# 01_MAIN.net
KiCad netlist of a schematic drawn in Altium Designer
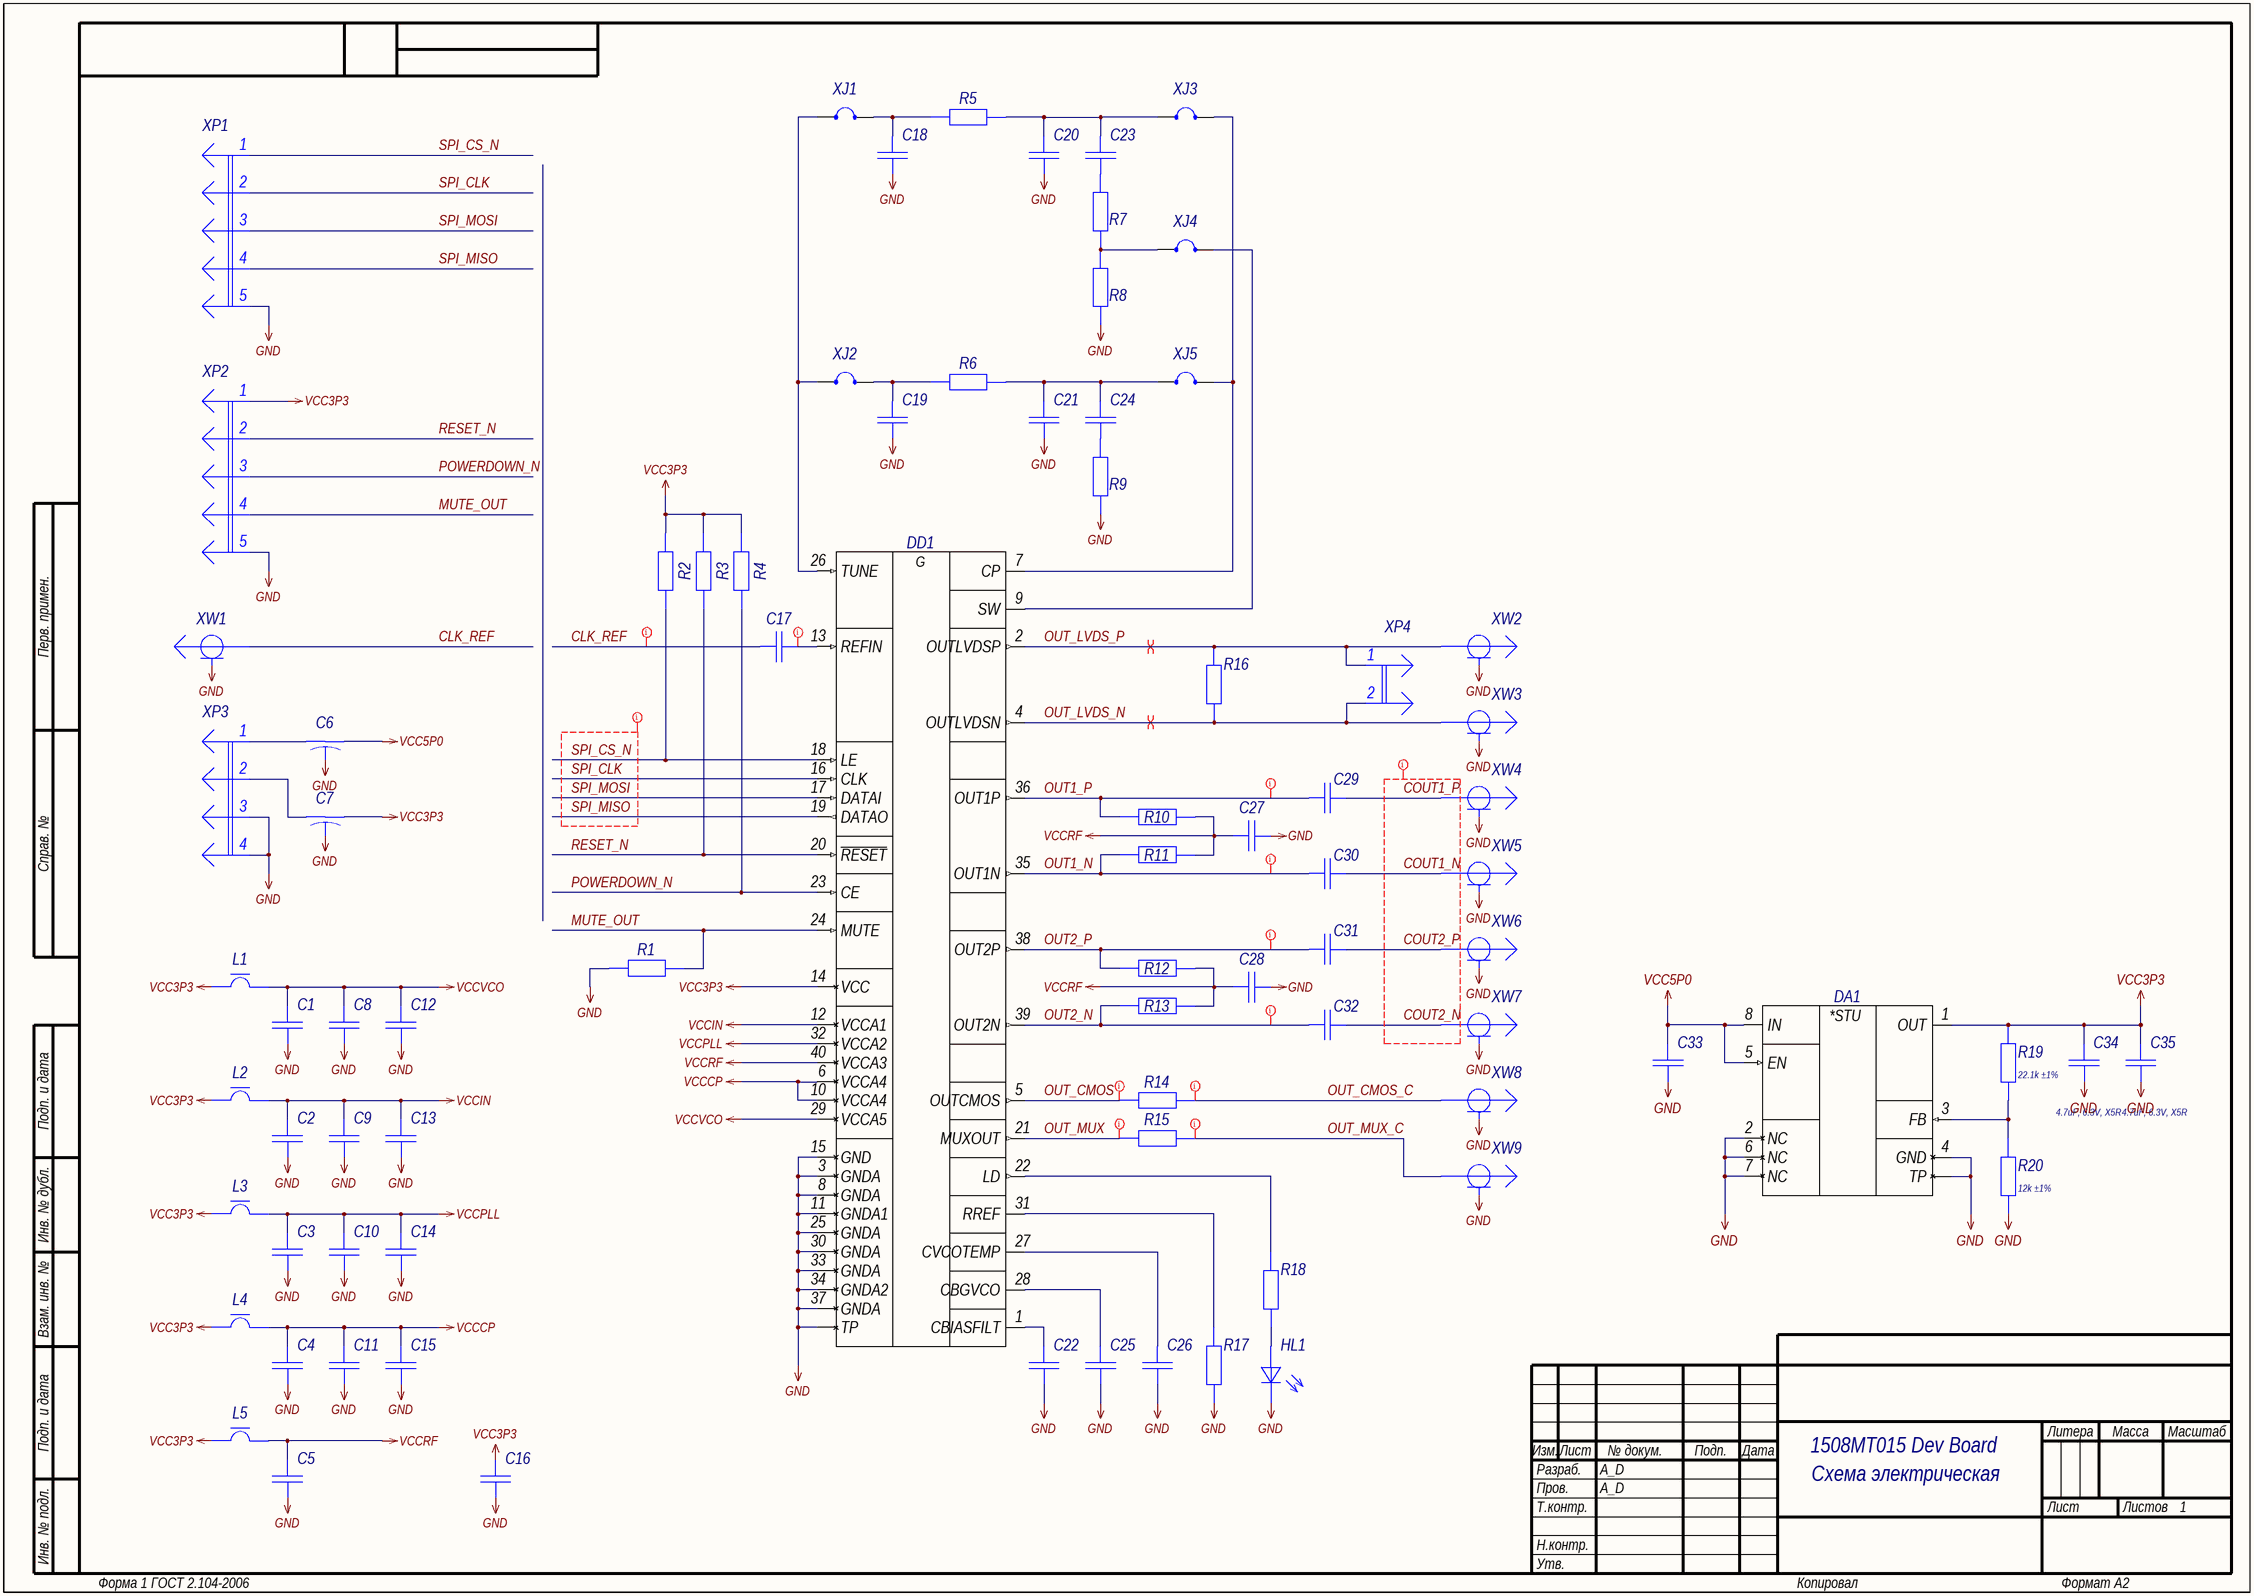
[diagram p0: 01_MAIN.SchDoc]

(export (version "E")
  (design (tool "Eeschema 10.0.6"))
  (components
    (comp (ref "C1")
      (value "Capacitor")
      (footprint "C0402_L")
      (fields
        (field (name "PART NUMBER") "GRM155C71A105KE11D")
        (field (name "VOLTAGE") "10V")
        (field (name "TOLERANCE") "±10%")
        (field (name "PUBLISHER") "Andrew Danich")
      )
      (libsource (lib "ADLib") (part "Capacitor"))
    )
    (comp (ref "C2")
      (value "Capacitor")
      (footprint "C0402_L")
      (fields
        (field (name "PART NUMBER") "GRM155C71A105KE11D")
        (field (name "VOLTAGE") "10V")
        (field (name "TOLERANCE") "±10%")
        (field (name "PUBLISHER") "Andrew Danich")
      )
      (libsource (lib "ADLib") (part "Capacitor"))
    )
    (comp (ref "C3")
      (value "Capacitor")
      (footprint "C0402_L")
      (fields
        (field (name "PART NUMBER") "GRM155C71A105KE11D")
        (field (name "VOLTAGE") "10V")
        (field (name "TOLERANCE") "±10%")
        (field (name "PUBLISHER") "Andrew Danich")
      )
      (libsource (lib "ADLib") (part "Capacitor"))
    )
    (comp (ref "C4")
      (value "Capacitor")
      (footprint "C0402_L")
      (fields
        (field (name "PART NUMBER") "GRM155C71A105KE11D")
        (field (name "VOLTAGE") "10V")
        (field (name "TOLERANCE") "±10%")
        (field (name "PUBLISHER") "Andrew Danich")
      )
      (libsource (lib "ADLib") (part "Capacitor"))
    )
    (comp (ref "C5")
      (value "Capacitor")
      (footprint "C0402_L")
      (fields
        (field (name "PART NUMBER") "GRM155C71A105KE11D")
        (field (name "VOLTAGE") "10V")
        (field (name "TOLERANCE") "±10%")
        (field (name "PUBLISHER") "Andrew Danich")
      )
      (libsource (lib "ADLib") (part "Capacitor"))
    )
    (comp (ref "C6")
      (value "CAP-FT_123")
      (footprint "NFM21PC")
      (fields
        (field (name "PART NUMBER") "NFM21PC474R1C3D")
        (field (name "TOLERANCE") "±20%")
        (field (name "MANUFACTURER") "Murata")
        (field (name "PUBLISHER") "Viktor Klishin")
      )
      (libsource (lib "ADLib") (part "CAP-FT_123"))
    )
    (comp (ref "C7")
      (value "CAP-FT_123")
      (footprint "NFM18PC_H080-Series")
      (fields
        (field (name "PART NUMBER") "NFM18PC105R0J3D")
        (field (name "TOLERANCE") "±20%")
        (field (name "MANUFACTURER") "Murata")
        (field (name "PUBLISHER") "Viktor Klishin")
      )
      (libsource (lib "ADLib") (part "CAP-FT_123"))
    )
    (comp (ref "C8")
      (value "Capacitor")
      (footprint "C0402_L")
      (fields
        (field (name "PART NUMBER") "GCM155R71C104KA55D")
        (field (name "VOLTAGE") "16V")
        (field (name "TOLERANCE") "±10%")
        (field (name "PUBLISHER") "Andrew Danich")
      )
      (libsource (lib "ADLib") (part "Capacitor"))
    )
    (comp (ref "C9")
      (value "Capacitor")
      (footprint "C0402_L")
      (fields
        (field (name "PART NUMBER") "GCM155R71C104KA55D")
        (field (name "VOLTAGE") "16V")
        (field (name "TOLERANCE") "±10%")
        (field (name "PUBLISHER") "Andrew Danich")
      )
      (libsource (lib "ADLib") (part "Capacitor"))
    )
    (comp (ref "C10")
      (value "Capacitor")
      (footprint "C0402_L")
      (fields
        (field (name "PART NUMBER") "GCM155R71C104KA55D")
        (field (name "VOLTAGE") "16V")
        (field (name "TOLERANCE") "±10%")
        (field (name "PUBLISHER") "Andrew Danich")
      )
      (libsource (lib "ADLib") (part "Capacitor"))
    )
    (comp (ref "C11")
      (value "Capacitor")
      (footprint "C0402_L")
      (fields
        (field (name "PART NUMBER") "GCM155R71C104KA55D")
        (field (name "VOLTAGE") "16V")
        (field (name "TOLERANCE") "±10%")
        (field (name "PUBLISHER") "Andrew Danich")
      )
      (libsource (lib "ADLib") (part "Capacitor"))
    )
    (comp (ref "C12")
      (value "Capacitor")
      (footprint "C0402_L")
      (fields
        (field (name "PART NUMBER") "GCM155R71E103KA37D")
        (field (name "VOLTAGE") "25V")
        (field (name "TOLERANCE") "±10%")
        (field (name "PUBLISHER") "Andrew Danich")
      )
      (libsource (lib "ADLib") (part "Capacitor"))
    )
    (comp (ref "C13")
      (value "Capacitor")
      (footprint "C0402_L")
      (fields
        (field (name "PART NUMBER") "GCM1555C1H101FA16D")
        (field (name "VOLTAGE") "50V")
        (field (name "TOLERANCE") "±1%")
        (field (name "PUBLISHER") "Andrew Danich")
      )
      (libsource (lib "ADLib") (part "Capacitor"))
    )
    (comp (ref "C14")
      (value "Capacitor")
      (footprint "C0402_L")
      (fields
        (field (name "PART NUMBER") "GCM1555C1H101FA16D")
        (field (name "VOLTAGE") "50V")
        (field (name "TOLERANCE") "±1%")
        (field (name "PUBLISHER") "Andrew Danich")
      )
      (libsource (lib "ADLib") (part "Capacitor"))
    )
    (comp (ref "C15")
      (value "Capacitor")
      (footprint "C0402_L")
      (fields
        (field (name "PART NUMBER") "GCM1555C1H101FA16D")
        (field (name "VOLTAGE") "50V")
        (field (name "TOLERANCE") "±1%")
        (field (name "PUBLISHER") "Andrew Danich")
      )
      (libsource (lib "ADLib") (part "Capacitor"))
    )
    (comp (ref "C16")
      (value "Capacitor")
      (footprint "C0402_L")
      (fields
        (field (name "PART NUMBER") "GRM155C71A105KE11D")
        (field (name "VOLTAGE") "10V")
        (field (name "TOLERANCE") "±10%")
        (field (name "PUBLISHER") "Andrew Danich")
      )
      (libsource (lib "ADLib") (part "Capacitor"))
    )
    (comp (ref "C17")
      (value "Capacitor")
      (footprint "C0402_L")
      (fields
        (field (name "PART NUMBER") "GCM155R71C104KA55D")
        (field (name "VOLTAGE") "16V")
        (field (name "TOLERANCE") "±10%")
        (field (name "PUBLISHER") "Andrew Danich")
      )
      (libsource (lib "ADLib") (part "Capacitor"))
    )
    (comp (ref "C18")
      (value "Capacitor")
      (footprint "C0402_L")
      (fields
        (field (name "PART NUMBER") "GRM1555C1H471JA01D")
        (field (name "VOLTAGE") "50V")
        (field (name "TOLERANCE") "±5%")
        (field (name "PUBLISHER") "Andrew Danich")
      )
      (libsource (lib "ADLib") (part "Capacitor"))
    )
    (comp (ref "C19")
      (value "Capacitor")
      (footprint "C0402_L")
      (fields
        (field (name "PART NUMBER") "GRM1555C1H471JA01D")
        (field (name "VOLTAGE") "50V")
        (field (name "TOLERANCE") "±5%")
        (field (name "PUBLISHER") "Andrew Danich")
      )
      (libsource (lib "ADLib") (part "Capacitor"))
    )
    (comp (ref "C20")
      (value "Capacitor")
      (footprint "C0402_L")
      (fields
        (field (name "PART NUMBER") "GRM1555C1H471JA01D")
        (field (name "VOLTAGE") "50V")
        (field (name "TOLERANCE") "±5%")
        (field (name "PUBLISHER") "Andrew Danich")
      )
      (libsource (lib "ADLib") (part "Capacitor"))
    )
    (comp (ref "C21")
      (value "Capacitor")
      (footprint "C0402_L")
      (fields
        (field (name "PART NUMBER") "GRM155R71H332KA01D")
        (field (name "VOLTAGE") "50V")
        (field (name "TOLERANCE") "±10%")
        (field (name "PUBLISHER") "Andrew Danich")
      )
      (libsource (lib "ADLib") (part "Capacitor"))
    )
    (comp (ref "C22")
      (value "Capacitor")
      (footprint "C0402_L")
      (fields
        (field (name "PART NUMBER") "GCM155R71E103KA37D")
        (field (name "VOLTAGE") "25V")
        (field (name "TOLERANCE") "±10%")
        (field (name "PUBLISHER") "Andrew Danich")
      )
      (libsource (lib "ADLib") (part "Capacitor"))
    )
    (comp (ref "C23")
      (value "Capacitor")
      (footprint "C0402_L")
      (fields
        (field (name "PART NUMBER") "GCM155R71E333KA55D")
        (field (name "VOLTAGE") "25V")
        (field (name "TOLERANCE") "±10%")
        (field (name "PUBLISHER") "Andrew Danich")
      )
      (libsource (lib "ADLib") (part "Capacitor"))
    )
    (comp (ref "C24")
      (value "Capacitor")
      (footprint "C0402_L")
      (fields
        (field (name "PART NUMBER") "GCM155R71C104KA55D")
        (field (name "VOLTAGE") "16V")
        (field (name "TOLERANCE") "±10%")
        (field (name "PUBLISHER") "Andrew Danich")
      )
      (libsource (lib "ADLib") (part "Capacitor"))
    )
    (comp (ref "C25")
      (value "Capacitor")
      (footprint "C0402_L")
      (fields
        (field (name "PART NUMBER") "GCM155R71C104KA55D")
        (field (name "VOLTAGE") "16V")
        (field (name "TOLERANCE") "±10%")
        (field (name "PUBLISHER") "Andrew Danich")
      )
      (libsource (lib "ADLib") (part "Capacitor"))
    )
    (comp (ref "C26")
      (value "Capacitor")
      (footprint "C0402_L")
      (fields
        (field (name "PART NUMBER") "GCM155R71C104KA55D")
        (field (name "VOLTAGE") "16V")
        (field (name "TOLERANCE") "±10%")
        (field (name "PUBLISHER") "Andrew Danich")
      )
      (libsource (lib "ADLib") (part "Capacitor"))
    )
    (comp (ref "C27")
      (value "Capacitor")
      (footprint "C0402_L")
      (fields
        (field (name "PART NUMBER") "GCM155R71E103KA37D")
        (field (name "VOLTAGE") "25V")
        (field (name "TOLERANCE") "±10%")
        (field (name "PUBLISHER") "Andrew Danich")
      )
      (libsource (lib "ADLib") (part "Capacitor"))
    )
    (comp (ref "C28")
      (value "Capacitor")
      (footprint "C0402_L")
      (fields
        (field (name "PART NUMBER") "GCM155R71E103KA37D")
        (field (name "VOLTAGE") "25V")
        (field (name "TOLERANCE") "±10%")
        (field (name "PUBLISHER") "Andrew Danich")
      )
      (libsource (lib "ADLib") (part "Capacitor"))
    )
    (comp (ref "C29")
      (value "Capacitor")
      (footprint "C0402_L")
      (fields
        (field (name "PART NUMBER") "GCM155R71E103KA37D")
        (field (name "VOLTAGE") "25V")
        (field (name "TOLERANCE") "±10%")
        (field (name "PUBLISHER") "Andrew Danich")
      )
      (libsource (lib "ADLib") (part "Capacitor"))
    )
    (comp (ref "C30")
      (value "Capacitor")
      (footprint "C0402_L")
      (fields
        (field (name "PART NUMBER") "GCM155R71E103KA37D")
        (field (name "VOLTAGE") "25V")
        (field (name "TOLERANCE") "±10%")
        (field (name "PUBLISHER") "Andrew Danich")
      )
      (libsource (lib "ADLib") (part "Capacitor"))
    )
    (comp (ref "C31")
      (value "Capacitor")
      (footprint "C0402_L")
      (fields
        (field (name "PART NUMBER") "GCM155R71E103KA37D")
        (field (name "VOLTAGE") "25V")
        (field (name "TOLERANCE") "±10%")
        (field (name "PUBLISHER") "Andrew Danich")
      )
      (libsource (lib "ADLib") (part "Capacitor"))
    )
    (comp (ref "C32")
      (value "Capacitor")
      (footprint "C0402_L")
      (fields
        (field (name "PART NUMBER") "GCM155R71E103KA37D")
        (field (name "VOLTAGE") "25V")
        (field (name "TOLERANCE") "±10%")
        (field (name "PUBLISHER") "Andrew Danich")
      )
      (libsource (lib "ADLib") (part "Capacitor"))
    )
    (comp (ref "C33")
      (value "Capacitor")
      (footprint "C0402_L")
      (fields
        (field (name "PART NUMBER") "GRM155C71A105KE11D")
        (field (name "VOLTAGE") "10V")
        (field (name "TOLERANCE") "±10%")
        (field (name "PUBLISHER") "Andrew Danich")
      )
      (libsource (lib "ADLib") (part "Capacitor"))
    )
    (comp (ref "C34")
      (value "Capacitor")
      (footprint "C0402_L")
      (fields
        (field (name "PART NUMBER") "GRM155R60J475ME87D")
        (field (name "VOLTAGE") "6.3V")
        (field (name "TOLERANCE") "±20%")
        (field (name "SCHEMATIC VALUE") "4.7uF, 6.3V, X5R")
        (field (name "PUBLISHER") "Andrew Danich")
      )
      (libsource (lib "ADLib") (part "Capacitor"))
    )
    (comp (ref "C35")
      (value "Capacitor")
      (footprint "C0402_L")
      (fields
        (field (name "PART NUMBER") "GRM155R60J475ME87D")
        (field (name "VOLTAGE") "6.3V")
        (field (name "TOLERANCE") "±20%")
        (field (name "SCHEMATIC VALUE") "4.7uF, 6.3V, X5R")
        (field (name "PUBLISHER") "Andrew Danich")
      )
      (libsource (lib "ADLib") (part "Capacitor"))
    )
    (comp (ref "DA1")
      (value "TPS73501DRB")
      (footprint "VSON-8_065P300X300X100_N")
      (fields
        (field (name "PART NUMBER") "TPS73501DRBR")
        (field (name "MANUFACTURER") "Texas Instruments")
        (field (name "PUBLISHER") "Andrew Danich")
      )
      (libsource (lib "ADLib") (part "TPS73501DRB"))
    )
    (comp (ref "DD1")
      (value "1508МТ015")
      (footprint "5164.40-1H3")
      (fields (field (name "MANUFACTURER") "Миландр") (field (name "PUBLISHER") "Andrew Danich"))
      (libsource (lib "ADLib_RUS") (part "1508МТ015"))
    )
    (comp (ref "HL1")
      (value "Text")
      (footprint "LD0603")
      (fields (field (name "PART NUMBER") "BL-LS0603GC") (field (name "PUBLISHER") "Andrew Danich"))
      (libsource (lib "ADLib") (part "Led-1"))
    )
    (comp (ref "L1")
      (value "FerriteBead")
      (footprint "L0402_L")
      (fields
        (field (name "PART NUMBER") "BLM15HD102SN1D")
        (field (name "TOLERANCE") "±25%")
        (field (name "MANUFACTURER") "Murata")
        (field (name "PUBLISHER") "Andrew Danich")
      )
      (libsource (lib "ADLib") (part "FerriteBead"))
    )
    (comp (ref "L2")
      (value "FerriteBead")
      (footprint "L0402_L")
      (fields
        (field (name "PART NUMBER") "BLM15HD102SN1D")
        (field (name "TOLERANCE") "±25%")
        (field (name "MANUFACTURER") "Murata")
        (field (name "PUBLISHER") "Andrew Danich")
      )
      (libsource (lib "ADLib") (part "FerriteBead"))
    )
    (comp (ref "L3")
      (value "FerriteBead")
      (footprint "L0402_L")
      (fields
        (field (name "PART NUMBER") "BLM15HD102SN1D")
        (field (name "TOLERANCE") "±25%")
        (field (name "MANUFACTURER") "Murata")
        (field (name "PUBLISHER") "Andrew Danich")
      )
      (libsource (lib "ADLib") (part "FerriteBead"))
    )
    (comp (ref "L4")
      (value "FerriteBead")
      (footprint "L0402_L")
      (fields
        (field (name "PART NUMBER") "BLM15HD102SN1D")
        (field (name "TOLERANCE") "±25%")
        (field (name "MANUFACTURER") "Murata")
        (field (name "PUBLISHER") "Andrew Danich")
      )
      (libsource (lib "ADLib") (part "FerriteBead"))
    )
    (comp (ref "L5")
      (value "FerriteBead")
      (footprint "L0402_L")
      (fields
        (field (name "PART NUMBER") "BLM15HD102SN1D")
        (field (name "TOLERANCE") "±25%")
        (field (name "MANUFACTURER") "Murata")
        (field (name "PUBLISHER") "Andrew Danich")
      )
      (libsource (lib "ADLib") (part "FerriteBead"))
    )
    (comp (ref "R1")
      (value "Resistor")
      (footprint "R0402_L")
      (fields
        (field (name "PART NUMBER") "RC0402JR-07100KL")
        (field (name "TOLERANCE") "±5%")
        (field (name "MANUFACTURER") "Yageo")
        (field (name "PUBLISHER") "Andrew Danich")
      )
      (libsource (lib "ADLib") (part "Resistor"))
    )
    (comp (ref "R2")
      (value "Resistor")
      (footprint "R0402_L")
      (fields
        (field (name "PART NUMBER") "RC0402JR-07100KL")
        (field (name "TOLERANCE") "±5%")
        (field (name "MANUFACTURER") "Yageo")
        (field (name "PUBLISHER") "Andrew Danich")
      )
      (libsource (lib "ADLib") (part "Resistor"))
    )
    (comp (ref "R3")
      (value "Resistor")
      (footprint "R0402_L")
      (fields
        (field (name "PART NUMBER") "RC0402JR-07100KL")
        (field (name "TOLERANCE") "±5%")
        (field (name "MANUFACTURER") "Yageo")
        (field (name "PUBLISHER") "Andrew Danich")
      )
      (libsource (lib "ADLib") (part "Resistor"))
    )
    (comp (ref "R4")
      (value "Resistor")
      (footprint "R0402_L")
      (fields
        (field (name "PART NUMBER") "RC0402JR-07100KL")
        (field (name "TOLERANCE") "±5%")
        (field (name "MANUFACTURER") "Yageo")
        (field (name "PUBLISHER") "Andrew Danich")
      )
      (libsource (lib "ADLib") (part "Resistor"))
    )
    (comp (ref "R5")
      (value "Resistor")
      (footprint "R0402_L")
      (fields
        (field (name "PART NUMBER") "RC0402FR-071KL")
        (field (name "TOLERANCE") "±1%")
        (field (name "MANUFACTURER") "Yageo")
        (field (name "PUBLISHER") "Andrew Danich")
      )
      (libsource (lib "ADLib") (part "Resistor"))
    )
    (comp (ref "R6")
      (value "Resistor")
      (footprint "R0402_L")
      (fields
        (field (name "PART NUMBER") "RC0402FR-071KL")
        (field (name "TOLERANCE") "±1%")
        (field (name "MANUFACTURER") "Yageo")
        (field (name "PUBLISHER") "Andrew Danich")
      )
      (libsource (lib "ADLib") (part "Resistor"))
    )
    (comp (ref "R7")
      (value "Resistor")
      (footprint "R0402_L")
      (fields
        (field (name "PART NUMBER") "RC0402FR-07499RL")
        (field (name "TOLERANCE") "±1%")
        (field (name "MANUFACTURER") "Yageo")
        (field (name "PUBLISHER") "Andrew Danich")
      )
      (libsource (lib "ADLib") (part "Resistor"))
    )
    (comp (ref "R8")
      (value "Resistor")
      (footprint "R0402_L")
      (fields
        (field (name "PART NUMBER") "RC0402FR-071KL")
        (field (name "TOLERANCE") "±1%")
        (field (name "MANUFACTURER") "Yageo")
        (field (name "PUBLISHER") "Andrew Danich")
      )
      (libsource (lib "ADLib") (part "Resistor"))
    )
    (comp (ref "R9")
      (value "Resistor")
      (footprint "R0402_L")
      (fields
        (field (name "PART NUMBER") "RC0402FR-07499RL")
        (field (name "TOLERANCE") "±1%")
        (field (name "MANUFACTURER") "Yageo")
        (field (name "PUBLISHER") "Andrew Danich")
      )
      (libsource (lib "ADLib") (part "Resistor"))
    )
    (comp (ref "R10")
      (value "Resistor")
      (footprint "R0402_L")
      (fields
        (field (name "PART NUMBER") "RC0402FR-0749R9L")
        (field (name "TOLERANCE") "±1%")
        (field (name "MANUFACTURER") "Yageo")
        (field (name "PUBLISHER") "Andrew Danich")
      )
      (libsource (lib "ADLib") (part "Resistor"))
    )
    (comp (ref "R11")
      (value "Resistor")
      (footprint "R0402_L")
      (fields
        (field (name "PART NUMBER") "RC0402FR-0749R9L")
        (field (name "TOLERANCE") "±1%")
        (field (name "MANUFACTURER") "Yageo")
        (field (name "PUBLISHER") "Andrew Danich")
      )
      (libsource (lib "ADLib") (part "Resistor"))
    )
    (comp (ref "R12")
      (value "Resistor")
      (footprint "R0402_L")
      (fields
        (field (name "PART NUMBER") "RC0402FR-0749R9L")
        (field (name "TOLERANCE") "±1%")
        (field (name "MANUFACTURER") "Yageo")
        (field (name "PUBLISHER") "Andrew Danich")
      )
      (libsource (lib "ADLib") (part "Resistor"))
    )
    (comp (ref "R13")
      (value "Resistor")
      (footprint "R0402_L")
      (fields
        (field (name "PART NUMBER") "RC0402FR-0749R9L")
        (field (name "TOLERANCE") "±1%")
        (field (name "MANUFACTURER") "Yageo")
        (field (name "PUBLISHER") "Andrew Danich")
      )
      (libsource (lib "ADLib") (part "Resistor"))
    )
    (comp (ref "R14")
      (value "Resistor")
      (footprint "R0402_L")
      (fields
        (field (name "PART NUMBER") "RC0402FR-07100RL")
        (field (name "TOLERANCE") "±1%")
        (field (name "MANUFACTURER") "Yageo")
        (field (name "PUBLISHER") "Andrew Danich")
      )
      (libsource (lib "ADLib") (part "Resistor"))
    )
    (comp (ref "R15")
      (value "Resistor")
      (footprint "R0402_L")
      (fields
        (field (name "PART NUMBER") "RC0402FR-07100RL")
        (field (name "TOLERANCE") "±1%")
        (field (name "MANUFACTURER") "Yageo")
        (field (name "PUBLISHER") "Andrew Danich")
      )
      (libsource (lib "ADLib") (part "Resistor"))
    )
    (comp (ref "R16")
      (value "Resistor")
      (footprint "R0402_L")
      (fields
        (field (name "PART NUMBER") "RC0402FR-07100RL")
        (field (name "TOLERANCE") "±1%")
        (field (name "MANUFACTURER") "Yageo")
        (field (name "PUBLISHER") "Andrew Danich")
      )
      (libsource (lib "ADLib") (part "Resistor"))
    )
    (comp (ref "R17")
      (value "Resistor")
      (footprint "R0402_L")
      (fields
        (field (name "PART NUMBER") "RC0402FR-075K1L")
        (field (name "TOLERANCE") "±1%")
        (field (name "MANUFACTURER") "Yageo")
        (field (name "PUBLISHER") "Andrew Danich")
      )
      (libsource (lib "ADLib") (part "Resistor"))
    )
    (comp (ref "R18")
      (value "Resistor")
      (footprint "R0402_L")
      (fields
        (field (name "PART NUMBER") "RC0402JR-071KL")
        (field (name "TOLERANCE") "±5%")
        (field (name "MANUFACTURER") "Yageo")
        (field (name "PUBLISHER") "Andrew Danich")
      )
      (libsource (lib "ADLib") (part "Resistor"))
    )
    (comp (ref "R19")
      (value "Resistor")
      (footprint "R0402_L")
      (fields
        (field (name "PART NUMBER") "RC0402FR-0722K1L")
        (field (name "TOLERANCE") "±1%")
        (field (name "MANUFACTURER") "Yageo")
        (field (name "SCHEMATIC VALUE") "22.1k ±1%")
        (field (name "PUBLISHER") "Andrew Danich")
      )
      (libsource (lib "ADLib") (part "Resistor"))
    )
    (comp (ref "R20")
      (value "Resistor")
      (footprint "R0402_L")
      (fields
        (field (name "PART NUMBER") "RC0402FR-0712KL")
        (field (name "TOLERANCE") "±1%")
        (field (name "MANUFACTURER") "Yageo")
        (field (name "SCHEMATIC VALUE") "12k ±1%")
        (field (name "PUBLISHER") "Andrew Danich")
      )
      (libsource (lib "ADLib") (part "Resistor"))
    )
    (comp (ref "XJ1")
      (value "Text")
      (footprint "JS-S0603-2x")
      (fields (field (name "PART NUMBER") "SolderJumper-SMT") (field (name "PUBLISHER") "Andrew Danich"))
      (libsource (lib "ADLib") (part "JMP-1-NOBOM"))
    )
    (comp (ref "XJ2")
      (value "Text")
      (footprint "JS-S0603-2x")
      (fields (field (name "PART NUMBER") "SolderJumper-SMT") (field (name "PUBLISHER") "Andrew Danich"))
      (libsource (lib "ADLib") (part "JMP-1-NOBOM"))
    )
    (comp (ref "XJ3")
      (value "Text")
      (footprint "JS-S0603-2x")
      (fields (field (name "PART NUMBER") "SolderJumper-SMT") (field (name "PUBLISHER") "Andrew Danich"))
      (libsource (lib "ADLib") (part "JMP-1-NOBOM"))
    )
    (comp (ref "XJ4")
      (value "Text")
      (footprint "JS-S0603-2x")
      (fields (field (name "PART NUMBER") "SolderJumper-SMT") (field (name "PUBLISHER") "Andrew Danich"))
      (libsource (lib "ADLib") (part "JMP-1-NOBOM"))
    )
    (comp (ref "XJ5")
      (value "Text")
      (footprint "JS-S0603-2x")
      (fields (field (name "PART NUMBER") "SolderJumper-SMT") (field (name "PUBLISHER") "Andrew Danich"))
      (libsource (lib "ADLib") (part "JMP-1-NOBOM"))
    )
    (comp (ref "XP1")
      (value "SPI")
      (footprint "PLS-5")
      (fields (field (name "PART NUMBER") "PLS-5") (field (name "PUBLISHER") "Andrew Danich"))
      (libsource (lib "ADLib") (part "Con-5-M"))
    )
    (comp (ref "XP2")
      (value "CTRL")
      (footprint "PLS-5")
      (fields (field (name "PART NUMBER") "PLS-5") (field (name "PUBLISHER") "Andrew Danich"))
      (libsource (lib "ADLib") (part "Con-5-M"))
    )
    (comp (ref "XP3")
      (value "POWER")
      (footprint "PLS-4")
      (fields (field (name "PART NUMBER") "PLS-4") (field (name "PUBLISHER") "Andrew Danich"))
      (libsource (lib "ADLib") (part "Con-4-M"))
    )
    (comp (ref "XP4")
      (value "LVDS")
      (footprint "PLS-2")
      (fields (field (name "PART NUMBER") "PLS-2") (field (name "PUBLISHER") "Andrew Danich"))
      (libsource (lib "ADLib") (part "Con-2-M"))
    )
    (comp (ref "XW1")
      (value "CLK REF")
      (footprint "MMCX-J-ST-TH1")
      (fields
        (field (name "PART NUMBER") "MMCX-J-H-ST-TH1")
        (field (name "MANUFACTURER") "Samtec")
        (field (name "PUBLISHER") "НТЦ \"Вектор\"")
      )
      (libsource (lib "ADLib") (part "Con-RF-M"))
    )
    (comp (ref "XW2")
      (value "LVDS+")
      (footprint "MMCX-J-ST-TH1")
      (fields
        (field (name "PART NUMBER") "MMCX-J-H-ST-TH1")
        (field (name "MANUFACTURER") "Samtec")
        (field (name "PUBLISHER") "НТЦ \"Вектор\"")
      )
      (libsource (lib "ADLib") (part "Con-RF-M"))
    )
    (comp (ref "XW3")
      (value "LVDS-")
      (footprint "MMCX-J-ST-TH1")
      (fields
        (field (name "PART NUMBER") "MMCX-J-H-ST-TH1")
        (field (name "MANUFACTURER") "Samtec")
        (field (name "PUBLISHER") "НТЦ \"Вектор\"")
      )
      (libsource (lib "ADLib") (part "Con-RF-M"))
    )
    (comp (ref "XW4")
      (value "OUT1+")
      (footprint "MMCX-J-ST-TH1")
      (fields
        (field (name "PART NUMBER") "MMCX-J-H-ST-TH1")
        (field (name "MANUFACTURER") "Samtec")
        (field (name "PUBLISHER") "НТЦ \"Вектор\"")
      )
      (libsource (lib "ADLib") (part "Con-RF-M"))
    )
    (comp (ref "XW5")
      (value "OUT1-")
      (footprint "MMCX-J-ST-TH1")
      (fields
        (field (name "PART NUMBER") "MMCX-J-H-ST-TH1")
        (field (name "MANUFACTURER") "Samtec")
        (field (name "PUBLISHER") "НТЦ \"Вектор\"")
      )
      (libsource (lib "ADLib") (part "Con-RF-M"))
    )
    (comp (ref "XW6")
      (value "OUT2+")
      (footprint "MMCX-J-ST-TH1")
      (fields
        (field (name "PART NUMBER") "MMCX-J-H-ST-TH1")
        (field (name "MANUFACTURER") "Samtec")
        (field (name "PUBLISHER") "НТЦ \"Вектор\"")
      )
      (libsource (lib "ADLib") (part "Con-RF-M"))
    )
    (comp (ref "XW7")
      (value "OUT2-")
      (footprint "MMCX-J-ST-TH1")
      (fields
        (field (name "PART NUMBER") "MMCX-J-H-ST-TH1")
        (field (name "MANUFACTURER") "Samtec")
        (field (name "PUBLISHER") "НТЦ \"Вектор\"")
      )
      (libsource (lib "ADLib") (part "Con-RF-M"))
    )
    (comp (ref "XW8")
      (value "CMOS")
      (footprint "MMCX-J-ST-TH1")
      (fields
        (field (name "PART NUMBER") "MMCX-J-H-ST-TH1")
        (field (name "MANUFACTURER") "Samtec")
        (field (name "PUBLISHER") "НТЦ \"Вектор\"")
      )
      (libsource (lib "ADLib") (part "Con-RF-M"))
    )
    (comp (ref "XW9")
      (value "MUX")
      (footprint "MMCX-J-ST-TH1")
      (fields
        (field (name "PART NUMBER") "MMCX-J-H-ST-TH1")
        (field (name "MANUFACTURER") "Samtec")
        (field (name "PUBLISHER") "НТЦ \"Вектор\"")
      )
      (libsource (lib "ADLib") (part "Con-RF-M"))
    )
  )
  (nets
    (net (code "1") (name "/CLK_REF") (class "Default")
      (node (ref "C17") (pin "2") (pinfunction "2_2") (pintype "passive"))
      (node (ref "XW1") (pin "1") (pintype "passive"))
    )
    (net (code "2") (name "/COUT1_N") (class "Default")
      (node (ref "C30") (pin "1") (pinfunction "1_1") (pintype "passive"))
      (node (ref "XW5") (pin "1") (pintype "passive"))
    )
    (net (code "3") (name "/COUT1_P") (class "Default")
      (node (ref "C29") (pin "1") (pinfunction "1_1") (pintype "passive"))
      (node (ref "XW4") (pin "1") (pintype "passive"))
    )
    (net (code "4") (name "/COUT2_N") (class "Default")
      (node (ref "C32") (pin "1") (pinfunction "1_1") (pintype "passive"))
      (node (ref "XW7") (pin "1") (pintype "passive"))
    )
    (net (code "5") (name "/COUT2_P") (class "Default")
      (node (ref "C31") (pin "1") (pinfunction "1_1") (pintype "passive"))
      (node (ref "XW6") (pin "1") (pintype "passive"))
    )
    (net (code "6") (name "/MUTE_OUT") (class "Default")
      (node (ref "DD1") (pin "24") (pinfunction "MUTE_24") (pintype "input"))
      (node (ref "R1") (pin "1") (pinfunction "1_1") (pintype "passive"))
      (node (ref "XP2") (pin "4") (pintype "passive"))
    )
    (net (code "7") (name "/OUT1_N") (class "Default")
      (node (ref "C30") (pin "2") (pinfunction "2_2") (pintype "passive"))
      (node (ref "DD1") (pin "35") (pinfunction "OUT1N_35") (pintype "output"))
      (node (ref "R11") (pin "1") (pinfunction "1_1") (pintype "passive"))
    )
    (net (code "8") (name "/OUT1_P") (class "Default")
      (node (ref "C29") (pin "2") (pinfunction "2_2") (pintype "passive"))
      (node (ref "DD1") (pin "36") (pinfunction "OUT1P_36") (pintype "output"))
      (node (ref "R10") (pin "1") (pinfunction "1_1") (pintype "passive"))
    )
    (net (code "9") (name "/OUT2_N") (class "Default")
      (node (ref "C32") (pin "2") (pinfunction "2_2") (pintype "passive"))
      (node (ref "DD1") (pin "39") (pinfunction "OUT2N_39") (pintype "output"))
      (node (ref "R13") (pin "1") (pinfunction "1_1") (pintype "passive"))
    )
    (net (code "10") (name "/OUT2_P") (class "Default")
      (node (ref "C31") (pin "2") (pinfunction "2_2") (pintype "passive"))
      (node (ref "DD1") (pin "38") (pinfunction "OUT2P_38") (pintype "output"))
      (node (ref "R12") (pin "1") (pinfunction "1_1") (pintype "passive"))
    )
    (net (code "11") (name "/OUT_CMOS") (class "Default")
      (node (ref "DD1") (pin "5") (pinfunction "OUTCMOS_5") (pintype "output"))
      (node (ref "R14") (pin "1") (pinfunction "1_1") (pintype "passive"))
    )
    (net (code "12") (name "/OUT_CMOS_C") (class "Default")
      (node (ref "R14") (pin "2") (pinfunction "2_2") (pintype "passive"))
      (node (ref "XW8") (pin "1") (pintype "passive"))
    )
    (net (code "13") (name "/OUT_LVDS_N") (class "Default")
      (node (ref "DD1") (pin "4") (pinfunction "OUTLVDSN_4") (pintype "output"))
      (node (ref "R16") (pin "1") (pinfunction "1_1") (pintype "passive"))
      (node (ref "XP4") (pin "2") (pintype "passive"))
      (node (ref "XW3") (pin "1") (pintype "passive"))
    )
    (net (code "14") (name "/OUT_LVDS_P") (class "Default")
      (node (ref "DD1") (pin "2") (pinfunction "OUTLVDSP_2") (pintype "output"))
      (node (ref "R16") (pin "2") (pinfunction "2_2") (pintype "passive"))
      (node (ref "XP4") (pin "1") (pintype "passive"))
      (node (ref "XW2") (pin "1") (pintype "passive"))
    )
    (net (code "15") (name "/OUT_MUX") (class "Default")
      (node (ref "DD1") (pin "21") (pinfunction "MUXOUT_21") (pintype "output"))
      (node (ref "R15") (pin "1") (pinfunction "1_1") (pintype "passive"))
    )
    (net (code "16") (name "/OUT_MUX_C") (class "Default")
      (node (ref "R15") (pin "2") (pinfunction "2_2") (pintype "passive"))
      (node (ref "XW9") (pin "1") (pintype "passive"))
    )
    (net (code "17") (name "/POWERDOWN_N") (class "Default")
      (node (ref "DD1") (pin "23") (pinfunction "CE_23") (pintype "input"))
      (node (ref "R4") (pin "1") (pinfunction "1_1") (pintype "passive"))
      (node (ref "XP2") (pin "3") (pintype "passive"))
    )
    (net (code "18") (name "/RESET_N") (class "Default")
      (node (ref "DD1") (pin "20") (pinfunction "~{RESET}_20") (pintype "input"))
      (node (ref "R3") (pin "1") (pinfunction "1_1") (pintype "passive"))
      (node (ref "XP2") (pin "2") (pintype "passive"))
    )
    (net (code "19") (name "/SPI_CLK") (class "Default")
      (node (ref "DD1") (pin "16") (pinfunction "CLK_16") (pintype "input"))
      (node (ref "XP1") (pin "2") (pintype "passive"))
    )
    (net (code "20") (name "/SPI_CS_N") (class "Default")
      (node (ref "DD1") (pin "18") (pinfunction "LE_18") (pintype "input"))
      (node (ref "R2") (pin "1") (pinfunction "1_1") (pintype "passive"))
      (node (ref "XP1") (pin "1") (pintype "passive"))
    )
    (net (code "21") (name "/SPI_MISO") (class "Default")
      (node (ref "DD1") (pin "19") (pinfunction "DATAO_19") (pintype "output"))
      (node (ref "XP1") (pin "4") (pintype "passive"))
    )
    (net (code "22") (name "/SPI_MOSI") (class "Default")
      (node (ref "DD1") (pin "17") (pinfunction "DATAI_17") (pintype "input"))
      (node (ref "XP1") (pin "3") (pintype "passive"))
    )
    (net (code "23") (name "GND") (class "Default")
      (node (ref "C1") (pin "1") (pinfunction "1_1") (pintype "passive"))
      (node (ref "C10") (pin "1") (pinfunction "1_1") (pintype "passive"))
      (node (ref "C11") (pin "1") (pinfunction "1_1") (pintype "passive"))
      (node (ref "C12") (pin "1") (pinfunction "1_1") (pintype "passive"))
      (node (ref "C13") (pin "1") (pinfunction "1_1") (pintype "passive"))
      (node (ref "C14") (pin "1") (pinfunction "1_1") (pintype "passive"))
      (node (ref "C15") (pin "1") (pinfunction "1_1") (pintype "passive"))
      (node (ref "C16") (pin "1") (pinfunction "1_1") (pintype "passive"))
      (node (ref "C18") (pin "1") (pinfunction "1_1") (pintype "passive"))
      (node (ref "C19") (pin "1") (pinfunction "1_1") (pintype "passive"))
      (node (ref "C2") (pin "1") (pinfunction "1_1") (pintype "passive"))
      (node (ref "C20") (pin "1") (pinfunction "1_1") (pintype "passive"))
      (node (ref "C21") (pin "1") (pinfunction "1_1") (pintype "passive"))
      (node (ref "C22") (pin "1") (pinfunction "1_1") (pintype "passive"))
      (node (ref "C25") (pin "1") (pinfunction "1_1") (pintype "passive"))
      (node (ref "C26") (pin "1") (pinfunction "1_1") (pintype "passive"))
      (node (ref "C27") (pin "1") (pinfunction "1_1") (pintype "passive"))
      (node (ref "C28") (pin "1") (pinfunction "1_1") (pintype "passive"))
      (node (ref "C3") (pin "1") (pinfunction "1_1") (pintype "passive"))
      (node (ref "C33") (pin "1") (pinfunction "1_1") (pintype "passive"))
      (node (ref "C34") (pin "1") (pinfunction "1_1") (pintype "passive"))
      (node (ref "C35") (pin "1") (pinfunction "1_1") (pintype "passive"))
      (node (ref "C4") (pin "1") (pinfunction "1_1") (pintype "passive"))
      (node (ref "C5") (pin "1") (pinfunction "1_1") (pintype "passive"))
      (node (ref "C6") (pin "2") (pinfunction "2_2") (pintype "passive"))
      (node (ref "C7") (pin "2") (pinfunction "2_2") (pintype "passive"))
      (node (ref "C8") (pin "1") (pinfunction "1_1") (pintype "passive"))
      (node (ref "C9") (pin "1") (pinfunction "1_1") (pintype "passive"))
      (node (ref "DA1") (pin "2") (pinfunction "NC_2") (pintype "passive"))
      (node (ref "DA1") (pin "4") (pinfunction "GND_4") (pintype "power_in"))
      (node (ref "DA1") (pin "6") (pinfunction "NC_6") (pintype "passive"))
      (node (ref "DA1") (pin "7") (pinfunction "NC_7") (pintype "passive"))
      (node (ref "DA1") (pin "TP") (pinfunction "TP_TP") (pintype "passive"))
      (node (ref "DD1") (pin "11") (pinfunction "GNDA1_11") (pintype "power_in"))
      (node (ref "DD1") (pin "15") (pinfunction "GND_15") (pintype "power_in"))
      (node (ref "DD1") (pin "25") (pinfunction "GNDA_25") (pintype "power_in"))
      (node (ref "DD1") (pin "3") (pinfunction "GNDA_3") (pintype "power_in"))
      (node (ref "DD1") (pin "30") (pinfunction "GNDA_30") (pintype "power_in"))
      (node (ref "DD1") (pin "33") (pinfunction "GNDA_33") (pintype "power_in"))
      (node (ref "DD1") (pin "34") (pinfunction "GNDA2_34") (pintype "power_in"))
      (node (ref "DD1") (pin "37") (pinfunction "GNDA_37") (pintype "power_in"))
      (node (ref "DD1") (pin "8") (pinfunction "GNDA_8") (pintype "power_in"))
      (node (ref "DD1") (pin "TP") (pinfunction "TP_TP") (pintype "power_in"))
      (node (ref "HL1") (pin "2") (pinfunction "К_2") (pintype "passive"))
      (node (ref "R1") (pin "2") (pinfunction "2_2") (pintype "passive"))
      (node (ref "R17") (pin "1") (pinfunction "1_1") (pintype "passive"))
      (node (ref "R20") (pin "1") (pinfunction "1_1") (pintype "passive"))
      (node (ref "R8") (pin "1") (pinfunction "1_1") (pintype "passive"))
      (node (ref "R9") (pin "1") (pinfunction "1_1") (pintype "passive"))
      (node (ref "XP1") (pin "5") (pintype "passive"))
      (node (ref "XP2") (pin "5") (pintype "passive"))
      (node (ref "XP3") (pin "3") (pintype "passive"))
      (node (ref "XP3") (pin "4") (pintype "passive"))
      (node (ref "XW1") (pin "2") (pintype "passive"))
      (node (ref "XW2") (pin "2") (pintype "passive"))
      (node (ref "XW3") (pin "2") (pintype "passive"))
      (node (ref "XW4") (pin "2") (pintype "passive"))
      (node (ref "XW5") (pin "2") (pintype "passive"))
      (node (ref "XW6") (pin "2") (pintype "passive"))
      (node (ref "XW7") (pin "2") (pintype "passive"))
      (node (ref "XW8") (pin "2") (pintype "passive"))
      (node (ref "XW9") (pin "2") (pintype "passive"))
    )
    (net (code "24") (name "Net-(C6-Pad1)") (class "Default")
      (node (ref "C6") (pin "1") (pinfunction "1_1") (pintype "passive"))
      (node (ref "XP3") (pin "1") (pintype "passive"))
    )
    (net (code "25") (name "Net-(C7-Pad1)") (class "Default")
      (node (ref "C7") (pin "1") (pinfunction "1_1") (pintype "passive"))
      (node (ref "XP3") (pin "2") (pintype "passive"))
    )
    (net (code "26") (name "Net-(C18-Pad2)") (class "Default")
      (node (ref "C18") (pin "2") (pinfunction "2_2") (pintype "passive"))
      (node (ref "R5") (pin "1") (pinfunction "1_1") (pintype "passive"))
      (node (ref "XJ1") (pin "2") (pinfunction "2_2") (pintype "passive"))
    )
    (net (code "27") (name "Net-(C19-Pad2)") (class "Default")
      (node (ref "C19") (pin "2") (pinfunction "2_2") (pintype "passive"))
      (node (ref "R6") (pin "1") (pinfunction "1_1") (pintype "passive"))
      (node (ref "XJ2") (pin "2") (pinfunction "2_2") (pintype "passive"))
    )
    (net (code "28") (name "Net-(C20-Pad2)") (class "Default")
      (node (ref "C20") (pin "2") (pinfunction "2_2") (pintype "passive"))
      (node (ref "C23") (pin "2") (pinfunction "2_2") (pintype "passive"))
      (node (ref "R5") (pin "2") (pinfunction "2_2") (pintype "passive"))
      (node (ref "XJ3") (pin "1") (pinfunction "1_1") (pintype "passive"))
    )
    (net (code "29") (name "Net-(C21-Pad2)") (class "Default")
      (node (ref "C21") (pin "2") (pinfunction "2_2") (pintype "passive"))
      (node (ref "C24") (pin "2") (pinfunction "2_2") (pintype "passive"))
      (node (ref "R6") (pin "2") (pinfunction "2_2") (pintype "passive"))
      (node (ref "XJ5") (pin "1") (pinfunction "1_1") (pintype "passive"))
    )
    (net (code "30") (name "Net-(C23-Pad1)") (class "Default")
      (node (ref "C23") (pin "1") (pinfunction "1_1") (pintype "passive"))
      (node (ref "R7") (pin "2") (pinfunction "2_2") (pintype "passive"))
    )
    (net (code "31") (name "Net-(C24-Pad1)") (class "Default")
      (node (ref "C24") (pin "1") (pinfunction "1_1") (pintype "passive"))
      (node (ref "R9") (pin "2") (pinfunction "2_2") (pintype "passive"))
    )
    (net (code "32") (name "Net-(DA1-FB)") (class "Default")
      (node (ref "DA1") (pin "3") (pinfunction "FB_3") (pintype "input"))
      (node (ref "R19") (pin "1") (pinfunction "1_1") (pintype "passive"))
      (node (ref "R20") (pin "2") (pinfunction "2_2") (pintype "passive"))
    )
    (net (code "33") (name "Net-(DD1-CBGVCO)") (class "Default")
      (node (ref "C25") (pin "2") (pinfunction "2_2") (pintype "passive"))
      (node (ref "DD1") (pin "28") (pinfunction "CBGVCO_28") (pintype "passive"))
    )
    (net (code "34") (name "Net-(DD1-CBIASFILT)") (class "Default")
      (node (ref "C22") (pin "2") (pinfunction "2_2") (pintype "passive"))
      (node (ref "DD1") (pin "1") (pinfunction "CBIASFILT_1") (pintype "passive"))
    )
    (net (code "35") (name "Net-(DD1-CP)") (class "Default")
      (node (ref "DD1") (pin "7") (pinfunction "CP_7") (pintype "passive"))
      (node (ref "XJ3") (pin "2") (pinfunction "2_2") (pintype "passive"))
      (node (ref "XJ5") (pin "2") (pinfunction "2_2") (pintype "passive"))
    )
    (net (code "36") (name "Net-(DD1-CVCOTEMP)") (class "Default")
      (node (ref "C26") (pin "2") (pinfunction "2_2") (pintype "passive"))
      (node (ref "DD1") (pin "27") (pinfunction "CVCOTEMP_27") (pintype "passive"))
    )
    (net (code "37") (name "Net-(DD1-LD)") (class "Default")
      (node (ref "DD1") (pin "22") (pinfunction "LD_22") (pintype "output"))
      (node (ref "R18") (pin "2") (pinfunction "2_2") (pintype "passive"))
    )
    (net (code "38") (name "Net-(DD1-REFIN)") (class "Default")
      (node (ref "C17") (pin "1") (pinfunction "1_1") (pintype "passive"))
      (node (ref "DD1") (pin "13") (pinfunction "REFIN_13") (pintype "input"))
    )
    (net (code "39") (name "Net-(DD1-RREF)") (class "Default")
      (node (ref "DD1") (pin "31") (pinfunction "RREF_31") (pintype "passive"))
      (node (ref "R17") (pin "2") (pinfunction "2_2") (pintype "passive"))
    )
    (net (code "40") (name "Net-(DD1-SW)") (class "Default")
      (node (ref "DD1") (pin "9") (pinfunction "SW_9") (pintype "passive"))
      (node (ref "XJ4") (pin "2") (pinfunction "2_2") (pintype "passive"))
    )
    (net (code "41") (name "Net-(DD1-TUNE)") (class "Default")
      (node (ref "DD1") (pin "26") (pinfunction "TUNE_26") (pintype "input"))
      (node (ref "XJ1") (pin "1") (pinfunction "1_1") (pintype "passive"))
      (node (ref "XJ2") (pin "1") (pinfunction "1_1") (pintype "passive"))
    )
    (net (code "42") (name "Net-(HL1-А)") (class "Default")
      (node (ref "HL1") (pin "1") (pinfunction "А_1") (pintype "passive"))
      (node (ref "R18") (pin "1") (pinfunction "1_1") (pintype "passive"))
    )
    (net (code "43") (name "Net-(R7-Pad1)") (class "Default")
      (node (ref "R7") (pin "1") (pinfunction "1_1") (pintype "passive"))
      (node (ref "R8") (pin "2") (pinfunction "2_2") (pintype "passive"))
      (node (ref "XJ4") (pin "1") (pinfunction "1_1") (pintype "passive"))
    )
    (net (code "44") (name "VCC3P3") (class "Default")
      (node (ref "C16") (pin "2") (pinfunction "2_2") (pintype "passive"))
      (node (ref "C34") (pin "2") (pinfunction "2_2") (pintype "passive"))
      (node (ref "C35") (pin "2") (pinfunction "2_2") (pintype "passive"))
      (node (ref "C7") (pin "3") (pinfunction "3_3") (pintype "passive"))
      (node (ref "DA1") (pin "1") (pinfunction "OUT_1") (pintype "power_in"))
      (node (ref "DD1") (pin "14") (pinfunction "VCC_14") (pintype "power_in"))
      (node (ref "L1") (pin "1") (pinfunction "1_1") (pintype "passive"))
      (node (ref "L2") (pin "1") (pinfunction "1_1") (pintype "passive"))
      (node (ref "L3") (pin "1") (pinfunction "1_1") (pintype "passive"))
      (node (ref "L4") (pin "1") (pinfunction "1_1") (pintype "passive"))
      (node (ref "L5") (pin "1") (pinfunction "1_1") (pintype "passive"))
      (node (ref "R19") (pin "2") (pinfunction "2_2") (pintype "passive"))
      (node (ref "R2") (pin "2") (pinfunction "2_2") (pintype "passive"))
      (node (ref "R3") (pin "2") (pinfunction "2_2") (pintype "passive"))
      (node (ref "R4") (pin "2") (pinfunction "2_2") (pintype "passive"))
      (node (ref "XP2") (pin "1") (pintype "passive"))
    )
    (net (code "45") (name "VCC5P0") (class "Default")
      (node (ref "C33") (pin "2") (pinfunction "2_2") (pintype "passive"))
      (node (ref "C6") (pin "3") (pinfunction "3_3") (pintype "passive"))
      (node (ref "DA1") (pin "5") (pinfunction "EN_5") (pintype "input"))
      (node (ref "DA1") (pin "8") (pinfunction "IN_8") (pintype "power_in"))
    )
    (net (code "46") (name "VCCCP") (class "Default")
      (node (ref "C11") (pin "2") (pinfunction "2_2") (pintype "passive"))
      (node (ref "C15") (pin "2") (pinfunction "2_2") (pintype "passive"))
      (node (ref "C4") (pin "2") (pinfunction "2_2") (pintype "passive"))
      (node (ref "DD1") (pin "10") (pinfunction "VCCA4_10") (pintype "power_in"))
      (node (ref "DD1") (pin "6") (pinfunction "VCCA4_6") (pintype "power_in"))
      (node (ref "L4") (pin "2") (pinfunction "2_2") (pintype "passive"))
    )
    (net (code "47") (name "VCCIN") (class "Default")
      (node (ref "C13") (pin "2") (pinfunction "2_2") (pintype "passive"))
      (node (ref "C2") (pin "2") (pinfunction "2_2") (pintype "passive"))
      (node (ref "C9") (pin "2") (pinfunction "2_2") (pintype "passive"))
      (node (ref "DD1") (pin "12") (pinfunction "VCCA1_12") (pintype "power_in"))
      (node (ref "L2") (pin "2") (pinfunction "2_2") (pintype "passive"))
    )
    (net (code "48") (name "VCCPLL") (class "Default")
      (node (ref "C10") (pin "2") (pinfunction "2_2") (pintype "passive"))
      (node (ref "C14") (pin "2") (pinfunction "2_2") (pintype "passive"))
      (node (ref "C3") (pin "2") (pinfunction "2_2") (pintype "passive"))
      (node (ref "DD1") (pin "32") (pinfunction "VCCA2_32") (pintype "power_in"))
      (node (ref "L3") (pin "2") (pinfunction "2_2") (pintype "passive"))
    )
    (net (code "49") (name "VCCRF") (class "Default")
      (node (ref "C27") (pin "2") (pinfunction "2_2") (pintype "passive"))
      (node (ref "C28") (pin "2") (pinfunction "2_2") (pintype "passive"))
      (node (ref "C5") (pin "2") (pinfunction "2_2") (pintype "passive"))
      (node (ref "DD1") (pin "40") (pinfunction "VCCA3_40") (pintype "power_in"))
      (node (ref "L5") (pin "2") (pinfunction "2_2") (pintype "passive"))
      (node (ref "R10") (pin "2") (pinfunction "2_2") (pintype "passive"))
      (node (ref "R11") (pin "2") (pinfunction "2_2") (pintype "passive"))
      (node (ref "R12") (pin "2") (pinfunction "2_2") (pintype "passive"))
      (node (ref "R13") (pin "2") (pinfunction "2_2") (pintype "passive"))
    )
    (net (code "50") (name "VCCVCO") (class "Default")
      (node (ref "C1") (pin "2") (pinfunction "2_2") (pintype "passive"))
      (node (ref "C12") (pin "2") (pinfunction "2_2") (pintype "passive"))
      (node (ref "C8") (pin "2") (pinfunction "2_2") (pintype "passive"))
      (node (ref "DD1") (pin "29") (pinfunction "VCCA5_29") (pintype "power_in"))
      (node (ref "L1") (pin "2") (pinfunction "2_2") (pintype "passive"))
    )
  )
)
